# RF_opamp.net
KiCad netlist of a schematic drawn in Altium Designer
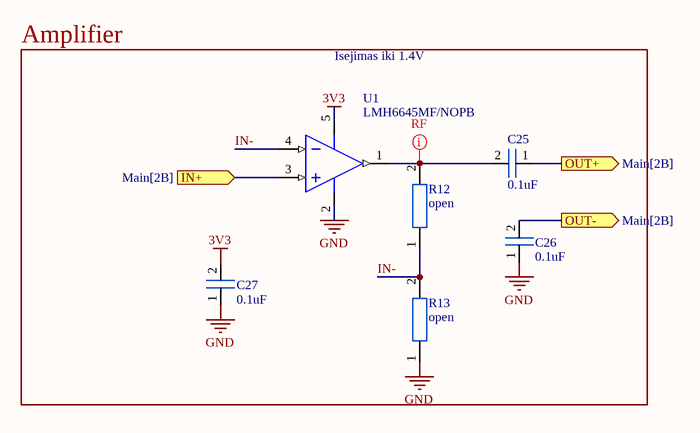
[diagram p0: RF_opamp.SchDoc]

(export (version "E")
  (design (tool "Eeschema 10.0.6"))
  (components
    (comp (ref "C25")
      (value "0.1uF")
      (footprint "0402_footprint")
      (description "0402 capacitor")
      (libsource (lib "Schlib1") (part "Capacitor_0402"))
    )
    (comp (ref "C26")
      (value "0.1uF")
      (footprint "0402_footprint")
      (description "0402 capacitor")
      (libsource (lib "Schlib1") (part "Capacitor_0402"))
    )
    (comp (ref "C27")
      (value "0.1uF")
      (footprint "0402_footprint")
      (description "0402 capacitor")
      (libsource (lib "Schlib1") (part "Capacitor_0402"))
    )
    (comp (ref "R12")
      (value "open")
      (footprint "0402_footprint")
      (libsource (lib "Schlib1") (part "Resistor_0402"))
    )
    (comp (ref "R13")
      (value "open")
      (footprint "0402_footprint")
      (libsource (lib "Schlib1") (part "Resistor_0402"))
    )
    (comp (ref "U1")
      (value "LMH6645MF/NOPB")
      (footprint "DBV0005A_N")
      (fields (field (name "MANUFACTURER") "Texas Instruments"))
      (libsource (lib "Altium Content Vault") (part "AMP-OPA-LM7121-5"))
    )
  )
  (nets
    (net (code "1") (name "/IN+") (class "Default")
      (node (ref "U1") (pin "3") (pinfunction "IN+_3") (pintype "input"))
    )
    (net (code "2") (name "/IN-") (class "Default")
      (node (ref "R12") (pin "1") (pinfunction "1_1") (pintype "passive"))
      (node (ref "R13") (pin "2") (pinfunction "2_2") (pintype "passive"))
      (node (ref "U1") (pin "4") (pinfunction "IN-_4") (pintype "input"))
    )
    (net (code "3") (name "/OUT+") (class "Default")
      (node (ref "C25") (pin "1") (pinfunction "1_1") (pintype "passive"))
    )
    (net (code "4") (name "/OUT-") (class "Default")
      (node (ref "C26") (pin "2") (pinfunction "2_2") (pintype "passive"))
    )
    (net (code "5") (name "3V3") (class "Default")
      (node (ref "C27") (pin "2") (pinfunction "2_2") (pintype "passive"))
      (node (ref "U1") (pin "5") (pinfunction "V+_5") (pintype "power_in"))
    )
    (net (code "6") (name "GND") (class "Default")
      (node (ref "C26") (pin "1") (pinfunction "1_1") (pintype "passive"))
      (node (ref "C27") (pin "1") (pinfunction "1_1") (pintype "passive"))
      (node (ref "R13") (pin "1") (pinfunction "1_1") (pintype "passive"))
      (node (ref "U1") (pin "2") (pinfunction "V-_2") (pintype "power_in"))
    )
    (net (code "7") (name "Net-(U1-OUT)") (class "Default")
      (node (ref "C25") (pin "2") (pinfunction "2_2") (pintype "passive"))
      (node (ref "R12") (pin "2") (pinfunction "2_2") (pintype "passive"))
      (node (ref "U1") (pin "1") (pinfunction "OUT_1") (pintype "output"))
    )
  )
)
